# mcu_node.net
KiCad netlist of a schematic drawn in Altium Designer
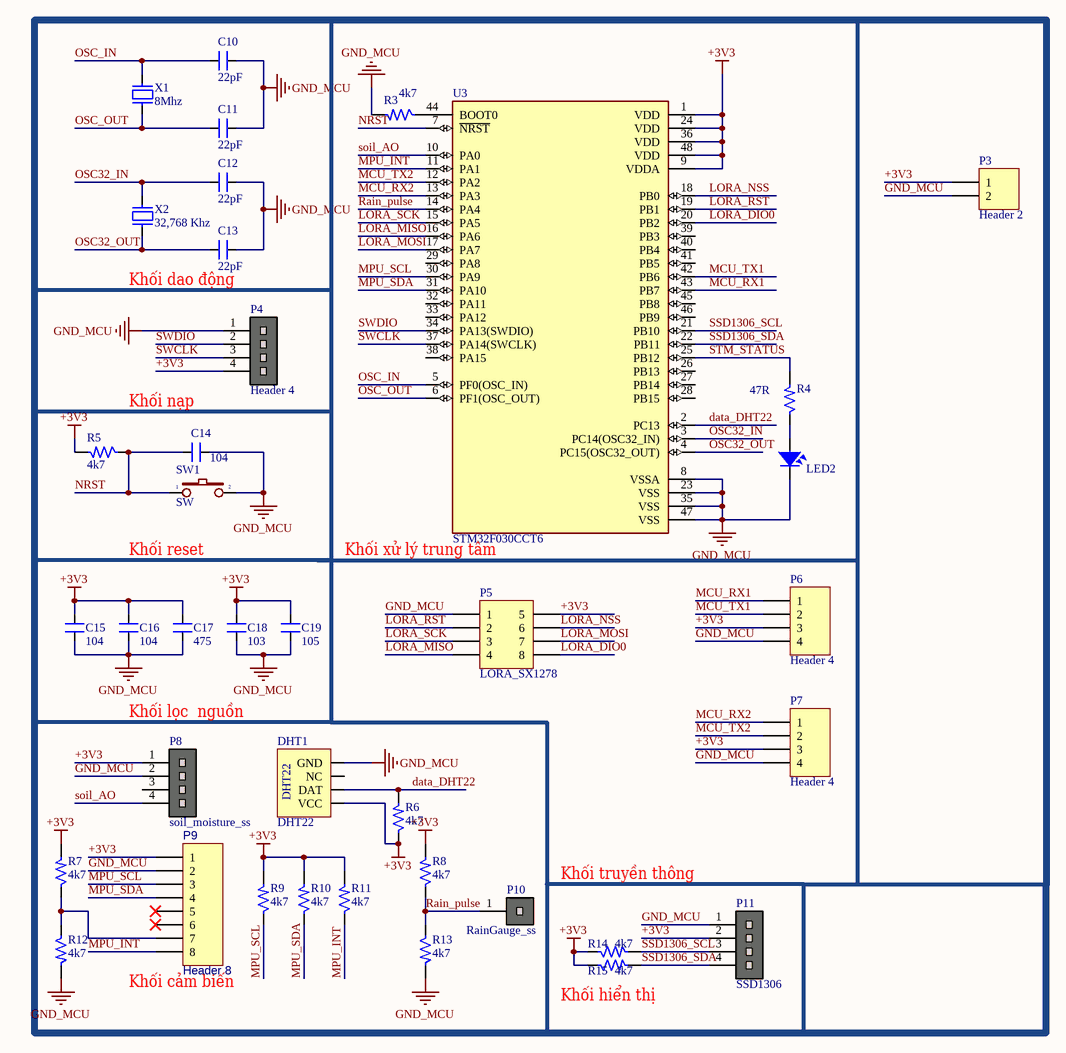
[diagram p0: mcu_node.SchDoc]

(export (version "E")
  (design (tool "Eeschema 10.0.6"))
  (components
    (comp (ref "C10")
      (value "22pF")
      (footprint "SM-0805")
      (description "Cap SMD")
      (libsource (lib "syhaunguyen") (part "CM"))
    )
    (comp (ref "C11")
      (value "22pF")
      (footprint "SM-0805")
      (description "Cap SMD")
      (libsource (lib "syhaunguyen") (part "CM"))
    )
    (comp (ref "C12")
      (value "22pF")
      (footprint "SM-0805")
      (description "Cap SMD")
      (libsource (lib "syhaunguyen") (part "CM"))
    )
    (comp (ref "C13")
      (value "22pF")
      (footprint "SM-0805")
      (description "Cap SMD")
      (libsource (lib "syhaunguyen") (part "CM"))
    )
    (comp (ref "C14")
      (value "104")
      (footprint "SM-0805")
      (description "Cap SMD")
      (libsource (lib "syhaunguyen") (part "CM"))
    )
    (comp (ref "C15")
      (value "104")
      (footprint "SM-0805")
      (description "Cap SMD")
      (libsource (lib "syhaunguyen") (part "CM"))
    )
    (comp (ref "C16")
      (value "104")
      (footprint "SM-0805")
      (description "Cap SMD")
      (libsource (lib "syhaunguyen") (part "CM"))
    )
    (comp (ref "C17")
      (value "475")
      (footprint "SM-0805")
      (description "Cap SMD")
      (libsource (lib "syhaunguyen") (part "CM"))
    )
    (comp (ref "C18")
      (value "103")
      (footprint "SM-0805")
      (description "Cap SMD")
      (libsource (lib "syhaunguyen") (part "CM"))
    )
    (comp (ref "C19")
      (value "105")
      (footprint "SM-0805")
      (description "Cap SMD")
      (libsource (lib "syhaunguyen") (part "CM"))
    )
    (comp (ref "DHT1")
      (value "DHT22")
      (footprint "DHT22")
      (fields
        (field (name "MANUFACTURER") "Würth Elektronik eiSos GmbH")
        (field (name "PARTNO") "613004143121")
        (field (name "CREATED BY") "Karrer Zheng")
      )
      (libsource (lib "TechMT.VN_Lib_Project v2") (part "DHT22"))
    )
    (comp (ref "LED2")
      (value "LED")
      (footprint "LED-0805-Green")
      (libsource (lib "TechMT.VN_Lib_Project v2") (part "LED SMD"))
    )
    (comp (ref "P3")
      (value "Header 2")
      (footprint "HDR1X2")
      (description "Header, 2-Pin")
      (fields (field (name "PUBLISHER") "Altium Limited"))
      (libsource (lib "Library AL") (part "Header 2"))
    )
    (comp (ref "P4")
      (value "Header 4")
      (footprint "HDR 1X4")
      (description "Header, 4-Pin")
      (libsource (lib "Ayric connectors") (part "Header 4"))
    )
    (comp (ref "P5")
      (value "LORA_SX1278")
      (footprint "HDR2X4_CEN")
      (description "Header, 4-Pin, Dual row")
      (fields (field (name "PUBLISHER") "Altium Limited"))
      (libsource (lib "Library AL") (part "Header 4X2A"))
    )
    (comp (ref "P6")
      (value "Header 4")
      (footprint "HDR1X4")
      (description "Header, 4-Pin")
      (fields (field (name "PUBLISHER") "Altium Limited"))
      (libsource (lib "Library AL") (part "Header 4"))
    )
    (comp (ref "P7")
      (value "Header 4")
      (footprint "HDR1X4")
      (description "Header, 4-Pin")
      (fields (field (name "PUBLISHER") "Altium Limited"))
      (libsource (lib "Library AL") (part "Header 4"))
    )
    (comp (ref "P8")
      (value "soil_moisture_ss")
      (footprint "HDR 1X4")
      (description "Header, 4-Pin")
      (libsource (lib "Ayric connectors") (part "Header 4"))
    )
    (comp (ref "P9")
      (value "Header 8")
      (footprint "HDR1X8")
      (description "Header, 8-Pin")
      (fields (field (name "PUBLISHER") "Altium Limited"))
      (libsource (lib "Library AL") (part "Header 8"))
    )
    (comp (ref "P10")
      (value "RainGauge_ss")
      (footprint "HDR 1X1")
      (description "Header, 1-Pin")
      (libsource (lib "Ayric connectors") (part "Header 1"))
    )
    (comp (ref "P11")
      (value "SSD1306")
      (footprint "HDR 1X4")
      (description "Header, 4-Pin")
      (libsource (lib "Ayric connectors") (part "Header 4"))
    )
    (comp (ref "R3")
      (value "4k7")
      (footprint "R-0805")
      (description "dien tro")
      (libsource (lib "oggy") (part "resistor"))
    )
    (comp (ref "R4")
      (value "47R")
      (footprint "R-0805")
      (description "dien tro")
      (libsource (lib "oggy") (part "resistor"))
    )
    (comp (ref "R5")
      (value "4k7")
      (footprint "R-0805")
      (description "dien tro")
      (libsource (lib "oggy") (part "resistor"))
    )
    (comp (ref "R6")
      (value "4k7")
      (footprint "R-0805")
      (description "dien tro")
      (libsource (lib "oggy") (part "resistor"))
    )
    (comp (ref "R7")
      (value "4k7")
      (footprint "R-0805")
      (description "dien tro")
      (libsource (lib "oggy") (part "resistor"))
    )
    (comp (ref "R8")
      (value "4k7")
      (footprint "R-0805")
      (description "dien tro")
      (libsource (lib "oggy") (part "resistor"))
    )
    (comp (ref "R9")
      (value "4k7")
      (footprint "R-0805")
      (description "dien tro")
      (libsource (lib "oggy") (part "resistor"))
    )
    (comp (ref "R10")
      (value "4k7")
      (footprint "R-0805")
      (description "dien tro")
      (libsource (lib "oggy") (part "resistor"))
    )
    (comp (ref "R11")
      (value "4k7")
      (footprint "R-0805")
      (description "dien tro")
      (libsource (lib "oggy") (part "resistor"))
    )
    (comp (ref "R12")
      (value "4k7")
      (footprint "R-0805")
      (description "dien tro")
      (libsource (lib "oggy") (part "resistor"))
    )
    (comp (ref "R13")
      (value "4k7")
      (footprint "R-0805")
      (description "dien tro")
      (libsource (lib "oggy") (part "resistor"))
    )
    (comp (ref "R14")
      (value "4k7")
      (footprint "R-0805")
      (description "dien tro")
      (libsource (lib "oggy") (part "resistor"))
    )
    (comp (ref "R15")
      (value "4k7")
      (footprint "R-0805")
      (description "dien tro")
      (libsource (lib "oggy") (part "resistor"))
    )
    (comp (ref "SW1")
      (value "SW")
      (footprint "SW1-SMD")
      (description "Switch button 2 pin")
      (libsource (lib "TechMT.VN_Lib_Project v2") (part "SW2"))
    )
    (comp (ref "U3")
      (value "STM32F030CCT6")
      (footprint "QFP50P900X900X160-48N")
      (description "ARMÂ® CortexÂ®-M0 STM32F0 Microcontroller IC 32-Bit 48MHz 256KB _256K x 8_ FLASH 48-LQFP _7x7_")
      (fields (field (name "MF") "STMicroelectronics") (field (name "DIGI-KEY_PART_NUMBER") "497-17332-2-ND"))
      (libsource (lib "STM32F030CCT6") (part "STM32F030CCT6"))
    )
    (comp (ref "X1")
      (value "8Mhz")
      (footprint "XT2")
      (description "Crystal For all Crystal 2pin.")
      (libsource (lib "syhaunguyen") (part "XT2"))
    )
    (comp (ref "X2")
      (value "32,768 Khz")
      (footprint "XT32k")
      (description "Crystal 32,768kHz for timer real")
      (libsource (lib "syhaunguyen") (part "XT32k"))
    )
  )
  (nets
    (net (code "1") (name "+3V3") (class "Default")
      (node (ref "C15") (pin "2") (pinfunction "2_2") (pintype "passive"))
      (node (ref "C16") (pin "2") (pinfunction "2_2") (pintype "passive"))
      (node (ref "C17") (pin "2") (pinfunction "2_2") (pintype "passive"))
      (node (ref "C18") (pin "2") (pinfunction "2_2") (pintype "passive"))
      (node (ref "C19") (pin "2") (pinfunction "2_2") (pintype "passive"))
      (node (ref "DHT1") (pin "1") (pinfunction "VCC_1") (pintype "passive"))
      (node (ref "P11") (pin "2") (pinfunction "2_2") (pintype "passive"))
      (node (ref "P3") (pin "1") (pinfunction "1_1") (pintype "passive"))
      (node (ref "P4") (pin "4") (pinfunction "4_4") (pintype "passive"))
      (node (ref "P5") (pin "5") (pinfunction "5_5") (pintype "passive"))
      (node (ref "P6") (pin "3") (pinfunction "3_3") (pintype "passive"))
      (node (ref "P7") (pin "3") (pinfunction "3_3") (pintype "passive"))
      (node (ref "P8") (pin "1") (pinfunction "1_1") (pintype "passive"))
      (node (ref "P9") (pin "1") (pinfunction "1_1") (pintype "passive"))
      (node (ref "R10") (pin "2") (pinfunction "2_2") (pintype "passive"))
      (node (ref "R11") (pin "2") (pinfunction "2_2") (pintype "passive"))
      (node (ref "R14") (pin "1") (pinfunction "1_1") (pintype "passive"))
      (node (ref "R15") (pin "1") (pinfunction "1_1") (pintype "passive"))
      (node (ref "R5") (pin "2") (pinfunction "2_2") (pintype "passive"))
      (node (ref "R6") (pin "1") (pinfunction "1_1") (pintype "passive"))
      (node (ref "R7") (pin "2") (pinfunction "2_2") (pintype "passive"))
      (node (ref "R8") (pin "2") (pinfunction "2_2") (pintype "passive"))
      (node (ref "R9") (pin "2") (pinfunction "2_2") (pintype "passive"))
      (node (ref "U3") (pin "1") (pinfunction "VDD_1") (pintype "power_in"))
      (node (ref "U3") (pin "24") (pinfunction "VDD_24") (pintype "power_in"))
      (node (ref "U3") (pin "36") (pinfunction "VDD_36") (pintype "power_in"))
      (node (ref "U3") (pin "48") (pinfunction "VDD_48") (pintype "power_in"))
      (node (ref "U3") (pin "9") (pinfunction "VDDA_9") (pintype "power_in"))
    )
    (net (code "2") (name "/LORA_DIO0") (class "Default")
      (node (ref "P5") (pin "8") (pinfunction "8_8") (pintype "passive"))
      (node (ref "U3") (pin "20") (pinfunction "PB2_20") (pintype "bidirectional"))
    )
    (net (code "3") (name "/LORA_MISO") (class "Default")
      (node (ref "P5") (pin "4") (pinfunction "4_4") (pintype "passive"))
      (node (ref "U3") (pin "16") (pinfunction "PA6_16") (pintype "bidirectional"))
    )
    (net (code "4") (name "/LORA_MOSI") (class "Default")
      (node (ref "P5") (pin "7") (pinfunction "7_7") (pintype "passive"))
      (node (ref "U3") (pin "17") (pinfunction "PA7_17") (pintype "bidirectional"))
    )
    (net (code "5") (name "/LORA_NSS") (class "Default")
      (node (ref "P5") (pin "6") (pinfunction "6_6") (pintype "passive"))
      (node (ref "U3") (pin "18") (pinfunction "PB0_18") (pintype "bidirectional"))
    )
    (net (code "6") (name "/LORA_RST") (class "Default")
      (node (ref "P5") (pin "2") (pinfunction "2_2") (pintype "passive"))
      (node (ref "U3") (pin "19") (pinfunction "PB1_19") (pintype "bidirectional"))
    )
    (net (code "7") (name "/LORA_SCK") (class "Default")
      (node (ref "P5") (pin "3") (pinfunction "3_3") (pintype "passive"))
      (node (ref "U3") (pin "15") (pinfunction "PA5_15") (pintype "bidirectional"))
    )
    (net (code "8") (name "/MCU_RX1") (class "Default")
      (node (ref "P6") (pin "1") (pinfunction "1_1") (pintype "passive"))
      (node (ref "U3") (pin "43") (pinfunction "PB7_43") (pintype "bidirectional"))
    )
    (net (code "9") (name "/MCU_RX2") (class "Default")
      (node (ref "P7") (pin "1") (pinfunction "1_1") (pintype "passive"))
      (node (ref "U3") (pin "13") (pinfunction "PA3_13") (pintype "bidirectional"))
    )
    (net (code "10") (name "/MCU_TX1") (class "Default")
      (node (ref "P6") (pin "2") (pinfunction "2_2") (pintype "passive"))
      (node (ref "U3") (pin "42") (pinfunction "PB6_42") (pintype "bidirectional"))
    )
    (net (code "11") (name "/MCU_TX2") (class "Default")
      (node (ref "P7") (pin "2") (pinfunction "2_2") (pintype "passive"))
      (node (ref "U3") (pin "12") (pinfunction "PA2_12") (pintype "bidirectional"))
    )
    (net (code "12") (name "/MPU_INT") (class "Default")
      (node (ref "P9") (pin "8") (pinfunction "8_8") (pintype "passive"))
      (node (ref "R11") (pin "1") (pinfunction "1_1") (pintype "passive"))
      (node (ref "U3") (pin "11") (pinfunction "PA1_11") (pintype "bidirectional"))
    )
    (net (code "13") (name "/MPU_SCL") (class "Default")
      (node (ref "P9") (pin "3") (pinfunction "3_3") (pintype "passive"))
      (node (ref "R9") (pin "1") (pinfunction "1_1") (pintype "passive"))
      (node (ref "U3") (pin "30") (pinfunction "PA9_30") (pintype "bidirectional"))
    )
    (net (code "14") (name "/MPU_SDA") (class "Default")
      (node (ref "P9") (pin "4") (pinfunction "4_4") (pintype "passive"))
      (node (ref "R10") (pin "1") (pinfunction "1_1") (pintype "passive"))
      (node (ref "U3") (pin "31") (pinfunction "PA10_31") (pintype "bidirectional"))
    )
    (net (code "15") (name "/NRST") (class "Default")
      (node (ref "C14") (pin "1") (pinfunction "1_1") (pintype "passive"))
      (node (ref "R5") (pin "1") (pinfunction "1_1") (pintype "passive"))
      (node (ref "SW1") (pin "1") (pinfunction "1_1") (pintype "passive"))
      (node (ref "U3") (pin "7") (pinfunction "~{NRST}_7") (pintype "bidirectional"))
    )
    (net (code "16") (name "/OSC32_IN") (class "Default")
      (node (ref "C12") (pin "2") (pinfunction "2_2") (pintype "passive"))
      (node (ref "U3") (pin "3") (pinfunction "PC14(OSC32_IN)_3") (pintype "bidirectional"))
      (node (ref "X2") (pin "2") (pinfunction "2_2") (pintype "passive"))
    )
    (net (code "17") (name "/OSC32_OUT") (class "Default")
      (node (ref "C13") (pin "2") (pinfunction "2_2") (pintype "passive"))
      (node (ref "U3") (pin "4") (pinfunction "PC15(OSC32_OUT)_4") (pintype "bidirectional"))
      (node (ref "X2") (pin "1") (pinfunction "1_1") (pintype "passive"))
    )
    (net (code "18") (name "/OSC_IN") (class "Default")
      (node (ref "C10") (pin "2") (pinfunction "2_2") (pintype "passive"))
      (node (ref "U3") (pin "5") (pinfunction "PF0(OSC_IN)_5") (pintype "bidirectional"))
      (node (ref "X1") (pin "2") (pinfunction "2_2") (pintype "passive"))
    )
    (net (code "19") (name "/OSC_OUT") (class "Default")
      (node (ref "C11") (pin "2") (pinfunction "2_2") (pintype "passive"))
      (node (ref "U3") (pin "6") (pinfunction "PF1(OSC_OUT)_6") (pintype "bidirectional"))
      (node (ref "X1") (pin "1") (pinfunction "1_1") (pintype "passive"))
    )
    (net (code "20") (name "/Rain_pulse") (class "Default")
      (node (ref "P10") (pin "1") (pinfunction "1_1") (pintype "passive"))
      (node (ref "R13") (pin "1") (pinfunction "1_1") (pintype "passive"))
      (node (ref "R8") (pin "1") (pinfunction "1_1") (pintype "passive"))
      (node (ref "U3") (pin "14") (pinfunction "PA4_14") (pintype "bidirectional"))
    )
    (net (code "21") (name "/SSD1306_SCL") (class "Default")
      (node (ref "P11") (pin "3") (pinfunction "3_3") (pintype "passive"))
      (node (ref "R14") (pin "2") (pinfunction "2_2") (pintype "passive"))
      (node (ref "U3") (pin "21") (pinfunction "PB10_21") (pintype "bidirectional"))
    )
    (net (code "22") (name "/SSD1306_SDA") (class "Default")
      (node (ref "P11") (pin "4") (pinfunction "4_4") (pintype "passive"))
      (node (ref "R15") (pin "2") (pinfunction "2_2") (pintype "passive"))
      (node (ref "U3") (pin "22") (pinfunction "PB11_22") (pintype "bidirectional"))
    )
    (net (code "23") (name "/STM_STATUS") (class "Default")
      (node (ref "R4") (pin "2") (pinfunction "2_2") (pintype "passive"))
      (node (ref "U3") (pin "25") (pinfunction "PB12_25") (pintype "bidirectional"))
    )
    (net (code "24") (name "/SWCLK") (class "Default")
      (node (ref "P4") (pin "3") (pinfunction "3_3") (pintype "passive"))
      (node (ref "U3") (pin "37") (pinfunction "PA14(SWCLK)_37") (pintype "bidirectional"))
    )
    (net (code "25") (name "/SWDIO") (class "Default")
      (node (ref "P4") (pin "2") (pinfunction "2_2") (pintype "passive"))
      (node (ref "U3") (pin "34") (pinfunction "PA13(SWDIO)_34") (pintype "bidirectional"))
    )
    (net (code "26") (name "/data_DHT22") (class "Default")
      (node (ref "DHT1") (pin "2") (pinfunction "DAT_2") (pintype "passive"))
      (node (ref "R6") (pin "2") (pinfunction "2_2") (pintype "passive"))
      (node (ref "U3") (pin "2") (pinfunction "PC13_2") (pintype "bidirectional"))
    )
    (net (code "27") (name "/soil_AO") (class "Default")
      (node (ref "P8") (pin "4") (pinfunction "4_4") (pintype "passive"))
      (node (ref "U3") (pin "10") (pinfunction "PA0_10") (pintype "bidirectional"))
    )
    (net (code "28") (name "GND_MCU") (class "Default")
      (node (ref "C10") (pin "1") (pinfunction "1_1") (pintype "passive"))
      (node (ref "C11") (pin "1") (pinfunction "1_1") (pintype "passive"))
      (node (ref "C12") (pin "1") (pinfunction "1_1") (pintype "passive"))
      (node (ref "C13") (pin "1") (pinfunction "1_1") (pintype "passive"))
      (node (ref "C14") (pin "2") (pinfunction "2_2") (pintype "passive"))
      (node (ref "C15") (pin "1") (pinfunction "1_1") (pintype "passive"))
      (node (ref "C16") (pin "1") (pinfunction "1_1") (pintype "passive"))
      (node (ref "C17") (pin "1") (pinfunction "1_1") (pintype "passive"))
      (node (ref "C18") (pin "1") (pinfunction "1_1") (pintype "passive"))
      (node (ref "C19") (pin "1") (pinfunction "1_1") (pintype "passive"))
      (node (ref "DHT1") (pin "4") (pinfunction "GND_4") (pintype "passive"))
      (node (ref "LED2") (pin "2") (pinfunction "2_2") (pintype "passive"))
      (node (ref "P11") (pin "1") (pinfunction "1_1") (pintype "passive"))
      (node (ref "P3") (pin "2") (pinfunction "2_2") (pintype "passive"))
      (node (ref "P4") (pin "1") (pinfunction "1_1") (pintype "passive"))
      (node (ref "P5") (pin "1") (pinfunction "1_1") (pintype "passive"))
      (node (ref "P6") (pin "4") (pinfunction "4_4") (pintype "passive"))
      (node (ref "P7") (pin "4") (pinfunction "4_4") (pintype "passive"))
      (node (ref "P8") (pin "2") (pinfunction "2_2") (pintype "passive"))
      (node (ref "P9") (pin "2") (pinfunction "2_2") (pintype "passive"))
      (node (ref "R12") (pin "2") (pinfunction "2_2") (pintype "passive"))
      (node (ref "R13") (pin "2") (pinfunction "2_2") (pintype "passive"))
      (node (ref "R3") (pin "2") (pinfunction "2_2") (pintype "passive"))
      (node (ref "SW1") (pin "2") (pinfunction "2_2") (pintype "passive"))
      (node (ref "U3") (pin "23") (pinfunction "VSS_23") (pintype "power_in"))
      (node (ref "U3") (pin "35") (pinfunction "VSS_35") (pintype "power_in"))
      (node (ref "U3") (pin "47") (pinfunction "VSS_47") (pintype "power_in"))
      (node (ref "U3") (pin "8") (pinfunction "VSSA_8") (pintype "power_in"))
    )
    (net (code "29") (name "Net-(LED2-Pad1)") (class "Default")
      (node (ref "LED2") (pin "1") (pinfunction "1_1") (pintype "passive"))
      (node (ref "R4") (pin "1") (pinfunction "1_1") (pintype "passive"))
    )
    (net (code "30") (name "Net-(P9-Pad7)") (class "Default")
      (node (ref "P9") (pin "7") (pinfunction "7_7") (pintype "passive"))
      (node (ref "R12") (pin "1") (pinfunction "1_1") (pintype "passive"))
      (node (ref "R7") (pin "1") (pinfunction "1_1") (pintype "passive"))
    )
    (net (code "31") (name "Net-(U3-BOOT0)") (class "Default")
      (node (ref "R3") (pin "1") (pinfunction "1_1") (pintype "passive"))
      (node (ref "U3") (pin "44") (pinfunction "BOOT0_44") (pintype "passive"))
    )
    (net (code "32") (name "unconnected-(DHT1-NC-Pad3)") (class "Default")
      (node (ref "DHT1") (pin "3") (pinfunction "NC_3") (pintype "passive"))
    )
    (net (code "33") (name "unconnected-(P8-Pad3)") (class "Default")
      (node (ref "P8") (pin "3") (pinfunction "3_3") (pintype "passive"))
    )
    (net (code "34") (name "unconnected-(P9-Pad5)") (class "Default")
      (node (ref "P9") (pin "5") (pinfunction "5_5") (pintype "passive+no_connect"))
    )
    (net (code "35") (name "unconnected-(P9-Pad6)") (class "Default")
      (node (ref "P9") (pin "6") (pinfunction "6_6") (pintype "passive+no_connect"))
    )
    (net (code "36") (name "unconnected-(U3-PA8-Pad29)") (class "Default")
      (node (ref "U3") (pin "29") (pinfunction "PA8_29") (pintype "bidirectional"))
    )
    (net (code "37") (name "unconnected-(U3-PA11-Pad32)") (class "Default")
      (node (ref "U3") (pin "32") (pinfunction "PA11_32") (pintype "bidirectional"))
    )
    (net (code "38") (name "unconnected-(U3-PA12-Pad33)") (class "Default")
      (node (ref "U3") (pin "33") (pinfunction "PA12_33") (pintype "bidirectional"))
    )
    (net (code "39") (name "unconnected-(U3-PA15-Pad38)") (class "Default")
      (node (ref "U3") (pin "38") (pinfunction "PA15_38") (pintype "bidirectional"))
    )
    (net (code "40") (name "unconnected-(U3-PB3-Pad39)") (class "Default")
      (node (ref "U3") (pin "39") (pinfunction "PB3_39") (pintype "bidirectional"))
    )
    (net (code "41") (name "unconnected-(U3-PB4-Pad40)") (class "Default")
      (node (ref "U3") (pin "40") (pinfunction "PB4_40") (pintype "bidirectional"))
    )
    (net (code "42") (name "unconnected-(U3-PB5-Pad41)") (class "Default")
      (node (ref "U3") (pin "41") (pinfunction "PB5_41") (pintype "bidirectional"))
    )
    (net (code "43") (name "unconnected-(U3-PB8-Pad45)") (class "Default")
      (node (ref "U3") (pin "45") (pinfunction "PB8_45") (pintype "bidirectional"))
    )
    (net (code "44") (name "unconnected-(U3-PB9-Pad46)") (class "Default")
      (node (ref "U3") (pin "46") (pinfunction "PB9_46") (pintype "bidirectional"))
    )
    (net (code "45") (name "unconnected-(U3-PB13-Pad26)") (class "Default")
      (node (ref "U3") (pin "26") (pinfunction "PB13_26") (pintype "bidirectional"))
    )
    (net (code "46") (name "unconnected-(U3-PB14-Pad27)") (class "Default")
      (node (ref "U3") (pin "27") (pinfunction "PB14_27") (pintype "bidirectional"))
    )
    (net (code "47") (name "unconnected-(U3-PB15-Pad28)") (class "Default")
      (node (ref "U3") (pin "28") (pinfunction "PB15_28") (pintype "bidirectional"))
    )
  )
)
